# Solar_supply.net
KiCad netlist of a schematic drawn in Altium Designer
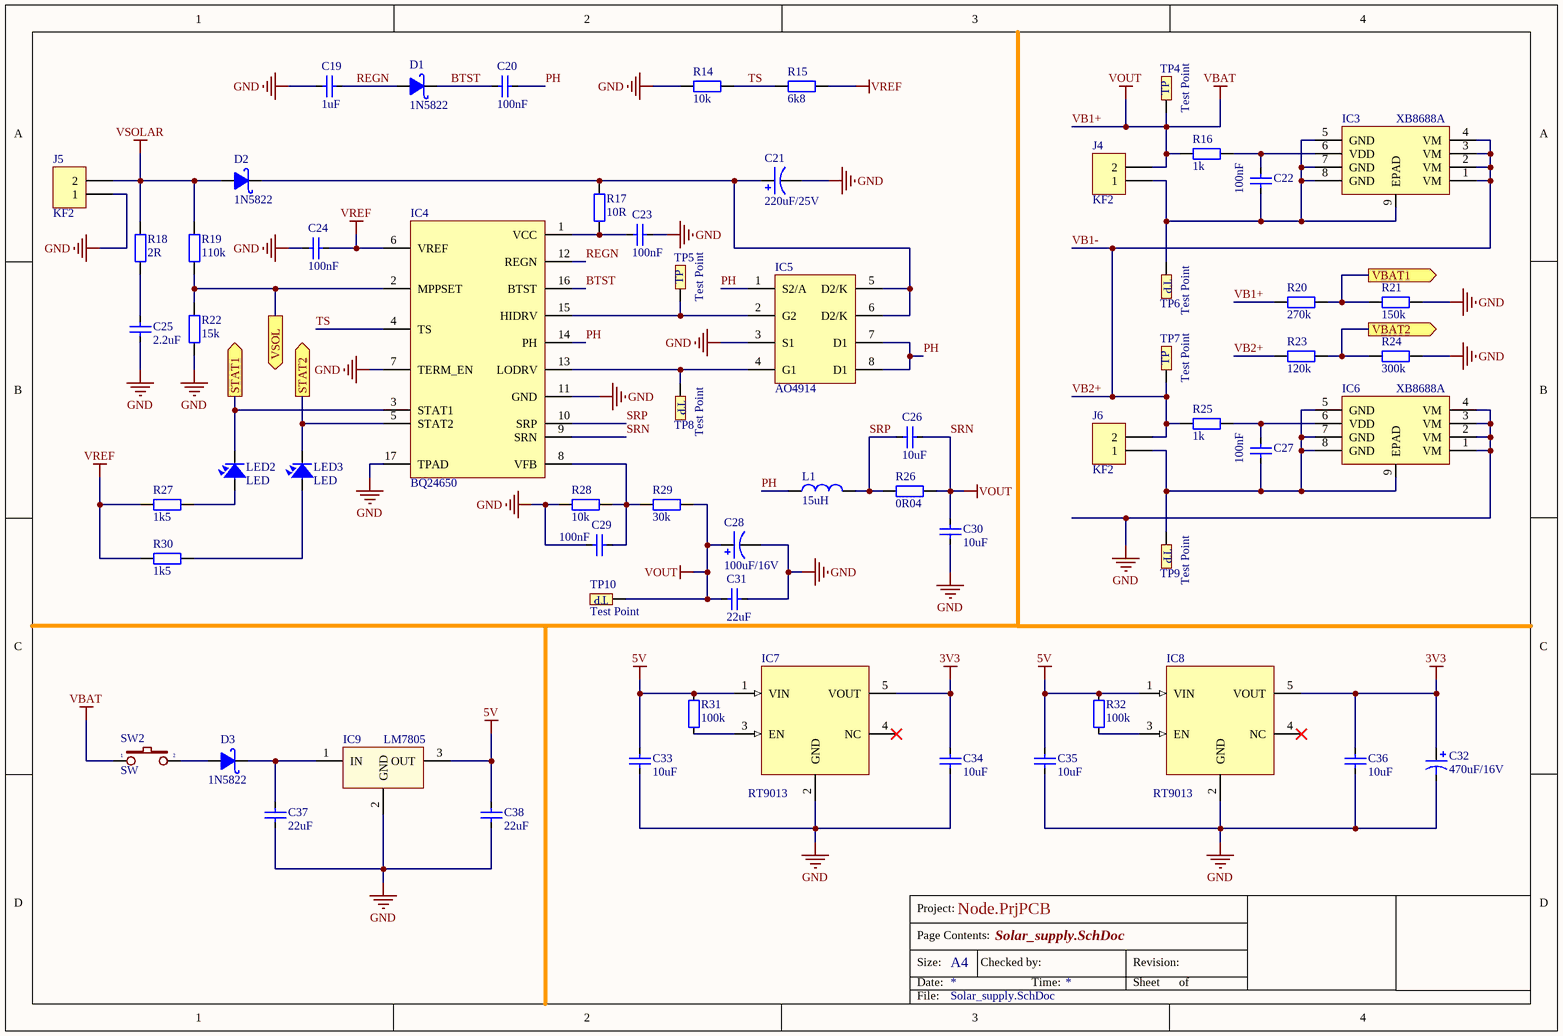
[diagram p0: Solar_supply.SchDoc]

(export (version "E")
  (design (tool "Eeschema 10.0.6"))
  (components
    (comp (ref "C19")
      (value "1uF")
      (footprint "CAP_0805")
      (description "Capacitor")
      (fields (field (name "PUBLISHER") "Altium Limited"))
      (libsource (lib "My Library") (part "CapSMD"))
    )
    (comp (ref "C20")
      (value "100nF")
      (footprint "CAP_0805")
      (description "Capacitor")
      (fields (field (name "PUBLISHER") "Altium Limited"))
      (libsource (lib "My Library") (part "CapSMD"))
    )
    (comp (ref "C21")
      (value "220uF/25V")
      (footprint "C5mm")
      (description "Polarized Capacitor (Axial)")
      (fields (field (name "PUBLISHER") "Altium Limited"))
      (libsource (lib "My Library") (part "Cap Pol"))
    )
    (comp (ref "C22")
      (value "100nF")
      (footprint "CAP_0805")
      (description "Capacitor")
      (fields (field (name "PUBLISHER") "Altium Limited"))
      (libsource (lib "My Library") (part "CapSMD"))
    )
    (comp (ref "C23")
      (value "100nF")
      (footprint "CAP_0805")
      (description "Capacitor")
      (fields (field (name "PUBLISHER") "Altium Limited"))
      (libsource (lib "My Library") (part "CapSMD"))
    )
    (comp (ref "C24")
      (value "100nF")
      (footprint "CAP_0805")
      (description "Capacitor")
      (fields (field (name "PUBLISHER") "Altium Limited"))
      (libsource (lib "My Library") (part "CapSMD"))
    )
    (comp (ref "C25")
      (value "2.2uF")
      (footprint "CAP_0805")
      (description "Capacitor")
      (fields (field (name "PUBLISHER") "Altium Limited"))
      (libsource (lib "My Library") (part "CapSMD"))
    )
    (comp (ref "C26")
      (value "10uF")
      (footprint "CAP_0805")
      (description "Capacitor")
      (fields (field (name "PUBLISHER") "Altium Limited"))
      (libsource (lib "My Library") (part "CapSMD"))
    )
    (comp (ref "C27")
      (value "100nF")
      (footprint "CAP_0805")
      (description "Capacitor")
      (fields (field (name "PUBLISHER") "Altium Limited"))
      (libsource (lib "My Library") (part "CapSMD"))
    )
    (comp (ref "C28")
      (value "100uF/16V")
      (footprint "C5mm")
      (description "Polarized Capacitor (Axial)")
      (fields (field (name "PUBLISHER") "Altium Limited"))
      (libsource (lib "My Library") (part "Cap Pol"))
    )
    (comp (ref "C29")
      (value "100nF")
      (footprint "CAP_0805")
      (description "Capacitor")
      (fields (field (name "PUBLISHER") "Altium Limited"))
      (libsource (lib "My Library") (part "CapSMD"))
    )
    (comp (ref "C30")
      (value "10uF")
      (footprint "CAP_0805")
      (description "Capacitor")
      (fields (field (name "PUBLISHER") "Altium Limited"))
      (libsource (lib "My Library") (part "CapSMD"))
    )
    (comp (ref "C31")
      (value "22uF")
      (footprint "CAP_0805")
      (description "Capacitor")
      (fields (field (name "PUBLISHER") "Altium Limited"))
      (libsource (lib "My Library") (part "CapSMD"))
    )
    (comp (ref "C32")
      (value "470uF/16V")
      (footprint "C8mm")
      (description "Polarized Capacitor (Axial)")
      (fields (field (name "PUBLISHER") "Altium Limited"))
      (libsource (lib "") (part "Cap Pol_1"))
    )
    (comp (ref "C33")
      (value "10uF")
      (footprint "CAP_0805")
      (description "Capacitor")
      (fields (field (name "PUBLISHER") "Altium Limited"))
      (libsource (lib "My Library") (part "CapSMD"))
    )
    (comp (ref "C34")
      (value "10uF")
      (footprint "CAP_0805")
      (description "Capacitor")
      (fields (field (name "PUBLISHER") "Altium Limited"))
      (libsource (lib "My Library") (part "CapSMD"))
    )
    (comp (ref "C35")
      (value "10uF")
      (footprint "CAP_0805")
      (description "Capacitor")
      (fields (field (name "PUBLISHER") "Altium Limited"))
      (libsource (lib "My Library") (part "CapSMD"))
    )
    (comp (ref "C36")
      (value "10uF")
      (footprint "CAP_0805")
      (description "Capacitor")
      (fields (field (name "PUBLISHER") "Altium Limited"))
      (libsource (lib "My Library") (part "CapSMD"))
    )
    (comp (ref "C37")
      (value "22uF")
      (footprint "CAP_0805")
      (description "Capacitor")
      (fields (field (name "PUBLISHER") "Altium Limited"))
      (libsource (lib "My Library") (part "CapSMD"))
    )
    (comp (ref "C38")
      (value "22uF")
      (footprint "CAP_0805")
      (description "Capacitor")
      (fields (field (name "PUBLISHER") "Altium Limited"))
      (libsource (lib "My Library") (part "CapSMD"))
    )
    (comp (ref "D1")
      (value "1N5822")
      (footprint "DIO-214AC(SMA)")
      (description "Schottky Rectifiers")
      (libsource (lib "My Library") (part "1N5822"))
    )
    (comp (ref "D2")
      (value "1N5822")
      (footprint "DIO-214AC(SMA)")
      (description "Schottky Rectifiers")
      (libsource (lib "My Library") (part "1N5822"))
    )
    (comp (ref "D3")
      (value "1N5822")
      (footprint "DIO-214AC(SMA)")
      (description "Schottky Rectifiers")
      (libsource (lib "My Library") (part "1N5822"))
    )
    (comp (ref "IC3")
      (value "XB8688A")
      (footprint "SOP8-PP")
      (description "One Cell Lithium-ion/Polymer Battery Protection IC")
      (libsource (lib "My Library") (part "XB8688"))
    )
    (comp (ref "IC4") (value "BQ24650") (footprint "VQFN-16") (libsource (lib "My Library") (part "BQ24650")))
    (comp (ref "IC5")
      (value "AO4914")
      (footprint "SOIC-8")
      (description "Dual N-Channel Enhancement Mode Field Effect Transistor with Schottky Diode")
      (libsource (lib "My Library") (part "AO4914"))
    )
    (comp (ref "IC6")
      (value "XB8688A")
      (footprint "SOP8-PP")
      (description "One Cell Lithium-ion/Polymer Battery Protection IC")
      (libsource (lib "My Library") (part "XB8688"))
    )
    (comp (ref "IC7")
      (value "RT9013")
      (footprint "SOT23-5")
      (description "RT9013-33GB IC REG LINEAR 3.3V 500mA SOT23-5")
      (libsource (lib "My Library") (part "RT9013"))
    )
    (comp (ref "IC8")
      (value "RT9013")
      (footprint "SOT23-5")
      (description "RT9013-33GB IC REG LINEAR 3.3V 500mA SOT23-5")
      (libsource (lib "My Library") (part "RT9013"))
    )
    (comp (ref "IC9")
      (value "LM7805")
      (footprint "TO-252")
      (description "LDO to 5V")
      (libsource (lib "My Library") (part "LM78xx"))
    )
    (comp (ref "J4")
      (value "KF2")
      (footprint "KF2-5.08")
      (fields
        (field (name "MANUFACTURER") "Würth Elektronik eiSos GmbH")
        (field (name "PARTNO") "691103110002")
        (field (name "CREATED BY") "Karrer Zheng")
      )
      (libsource (lib "My Library") (part "KF2"))
    )
    (comp (ref "J5")
      (value "KF2")
      (footprint "KF2-5.08")
      (fields
        (field (name "MANUFACTURER") "Würth Elektronik eiSos GmbH")
        (field (name "PARTNO") "691103110002")
        (field (name "CREATED BY") "Karrer Zheng")
      )
      (libsource (lib "My Library") (part "KF2"))
    )
    (comp (ref "J6")
      (value "KF2")
      (footprint "KF2-5.08")
      (fields
        (field (name "MANUFACTURER") "Würth Elektronik eiSos GmbH")
        (field (name "PARTNO") "691103110002")
        (field (name "CREATED BY") "Karrer Zheng")
      )
      (libsource (lib "My Library") (part "KF2"))
    )
    (comp (ref "L1")
      (value "15uH")
      (footprint "L-SMD-M-7.3x4.5")
      (description "Inductor")
      (libsource (lib "My Library") (part "Inductor"))
    )
    (comp (ref "LED2")
      (value "LED")
      (footprint "LED-0805-Red")
      (description "LED Single colour Green and Red")
      (libsource (lib "My Library") (part "LED"))
    )
    (comp (ref "LED3")
      (value "LED")
      (footprint "LED-0805-Orange")
      (description "LED Single colour Green and Red")
      (libsource (lib "My Library") (part "LED"))
    )
    (comp (ref "R14")
      (value "10k")
      (footprint "RES-SMD-0805")
      (description "Resistor SMD")
      (fields
        (field (name "MANUFACTURER") "Generic Components")
        (field (name "PUBLISHER") "Altium Hobart Technology Centre")
      )
      (libsource (lib "My Library") (part "Resistor - SMD"))
    )
    (comp (ref "R15")
      (value "6k8")
      (footprint "RES-SMD-0805")
      (description "Resistor SMD")
      (fields
        (field (name "MANUFACTURER") "Generic Components")
        (field (name "PUBLISHER") "Altium Hobart Technology Centre")
      )
      (libsource (lib "My Library") (part "Resistor - SMD"))
    )
    (comp (ref "R16")
      (value "1k")
      (footprint "RES-SMD-0805")
      (description "Resistor SMD")
      (fields
        (field (name "MANUFACTURER") "Generic Components")
        (field (name "PUBLISHER") "Altium Hobart Technology Centre")
      )
      (libsource (lib "My Library") (part "Resistor - SMD"))
    )
    (comp (ref "R17")
      (value "10R")
      (footprint "RES-SMD-0805")
      (description "Resistor SMD")
      (fields
        (field (name "MANUFACTURER") "Generic Components")
        (field (name "PUBLISHER") "Altium Hobart Technology Centre")
      )
      (libsource (lib "My Library") (part "Resistor - SMD"))
    )
    (comp (ref "R18")
      (value "2R")
      (footprint "RES-SMD-0805")
      (description "Resistor SMD")
      (fields
        (field (name "MANUFACTURER") "Generic Components")
        (field (name "PUBLISHER") "Altium Hobart Technology Centre")
      )
      (libsource (lib "My Library") (part "Resistor - SMD"))
    )
    (comp (ref "R19")
      (value "110k")
      (footprint "RES-SMD-0805")
      (description "Resistor SMD")
      (fields
        (field (name "MANUFACTURER") "Generic Components")
        (field (name "PUBLISHER") "Altium Hobart Technology Centre")
      )
      (libsource (lib "My Library") (part "Resistor - SMD"))
    )
    (comp (ref "R20")
      (value "270k")
      (footprint "RES-SMD-0805")
      (description "Resistor SMD")
      (fields
        (field (name "MANUFACTURER") "Generic Components")
        (field (name "PUBLISHER") "Altium Hobart Technology Centre")
      )
      (libsource (lib "My Library") (part "Resistor - SMD"))
    )
    (comp (ref "R21")
      (value "150k")
      (footprint "RES-SMD-0805")
      (description "Resistor SMD")
      (fields
        (field (name "MANUFACTURER") "Generic Components")
        (field (name "PUBLISHER") "Altium Hobart Technology Centre")
      )
      (libsource (lib "My Library") (part "Resistor - SMD"))
    )
    (comp (ref "R22")
      (value "15k")
      (footprint "RES-SMD-0805")
      (description "Resistor SMD")
      (fields
        (field (name "MANUFACTURER") "Generic Components")
        (field (name "PUBLISHER") "Altium Hobart Technology Centre")
      )
      (libsource (lib "My Library") (part "Resistor - SMD"))
    )
    (comp (ref "R23")
      (value "120k")
      (footprint "RES-SMD-0805")
      (description "Resistor SMD")
      (fields
        (field (name "MANUFACTURER") "Generic Components")
        (field (name "PUBLISHER") "Altium Hobart Technology Centre")
      )
      (libsource (lib "My Library") (part "Resistor - SMD"))
    )
    (comp (ref "R24")
      (value "300k")
      (footprint "RES-SMD-0805")
      (description "Resistor SMD")
      (fields
        (field (name "MANUFACTURER") "Generic Components")
        (field (name "PUBLISHER") "Altium Hobart Technology Centre")
      )
      (libsource (lib "My Library") (part "Resistor - SMD"))
    )
    (comp (ref "R25")
      (value "1k")
      (footprint "RES-SMD-0805")
      (description "Resistor SMD")
      (fields
        (field (name "MANUFACTURER") "Generic Components")
        (field (name "PUBLISHER") "Altium Hobart Technology Centre")
      )
      (libsource (lib "My Library") (part "Resistor - SMD"))
    )
    (comp (ref "R26")
      (value "0R04")
      (footprint "RES-SMD-2512")
      (description "Resistor SMD")
      (fields
        (field (name "MANUFACTURER") "Generic Components")
        (field (name "PUBLISHER") "Altium Hobart Technology Centre")
      )
      (libsource (lib "My Library") (part "Resistor - SMD"))
    )
    (comp (ref "R27")
      (value "1k5")
      (footprint "RES-SMD-0805")
      (description "Resistor SMD")
      (fields
        (field (name "MANUFACTURER") "Generic Components")
        (field (name "PUBLISHER") "Altium Hobart Technology Centre")
      )
      (libsource (lib "My Library") (part "Resistor - SMD"))
    )
    (comp (ref "R28")
      (value "10k")
      (footprint "RES-SMD-0805")
      (description "Resistor SMD")
      (fields
        (field (name "MANUFACTURER") "Generic Components")
        (field (name "PUBLISHER") "Altium Hobart Technology Centre")
      )
      (libsource (lib "My Library") (part "Resistor - SMD"))
    )
    (comp (ref "R29")
      (value "30k")
      (footprint "RES-SMD-0805")
      (description "Resistor SMD")
      (fields
        (field (name "MANUFACTURER") "Generic Components")
        (field (name "PUBLISHER") "Altium Hobart Technology Centre")
      )
      (libsource (lib "My Library") (part "Resistor - SMD"))
    )
    (comp (ref "R30")
      (value "1k5")
      (footprint "RES-SMD-0805")
      (description "Resistor SMD")
      (fields
        (field (name "MANUFACTURER") "Generic Components")
        (field (name "PUBLISHER") "Altium Hobart Technology Centre")
      )
      (libsource (lib "My Library") (part "Resistor - SMD"))
    )
    (comp (ref "R31")
      (value "100k")
      (footprint "RES-SMD-0805")
      (description "Resistor")
      (fields
        (field (name "MANUFACTURER") "Generic Components")
        (field (name "PUBLISHER") "Altium Hobart Technology Centre")
      )
      (libsource (lib "") (part "Resistor - SMD_1"))
    )
    (comp (ref "R32")
      (value "100k")
      (footprint "RES-SMD-0805")
      (description "Resistor")
      (fields
        (field (name "MANUFACTURER") "Generic Components")
        (field (name "PUBLISHER") "Altium Hobart Technology Centre")
      )
      (libsource (lib "") (part "Resistor - SMD_1"))
    )
    (comp (ref "SW2")
      (value "SW")
      (footprint "SW2")
      (description "Switch button 2 pin")
      (libsource (lib "My Library") (part "SW2"))
    )
    (comp (ref "TP4")
      (value "Test Point")
      (footprint "TP_SMD")
      (description "CONNECT 1")
      (libsource (lib "My Library") (part "TP"))
    )
    (comp (ref "TP5")
      (value "Test Point")
      (footprint "TP_SMD")
      (description "CONNECT 1")
      (libsource (lib "My Library") (part "TP"))
    )
    (comp (ref "TP6")
      (value "Test Point")
      (footprint "TP_SMD")
      (description "CONNECT 1")
      (libsource (lib "") (part "TP_1"))
    )
    (comp (ref "TP7")
      (value "Test Point")
      (footprint "TP_SMD")
      (description "CONNECT 1")
      (libsource (lib "My Library") (part "TP"))
    )
    (comp (ref "TP8")
      (value "Test Point")
      (footprint "TP_SMD")
      (description "CONNECT 1")
      (libsource (lib "") (part "TP_1"))
    )
    (comp (ref "TP9")
      (value "Test Point")
      (footprint "TP_SMD")
      (description "CONNECT 1")
      (libsource (lib "") (part "TP_1"))
    )
    (comp (ref "TP10")
      (value "Test Point")
      (footprint "TP_SMD")
      (description "CONNECT 1")
      (libsource (lib "") (part "TP_2"))
    )
  )
  (nets
    (net (code "1") (name "/BTST") (class "Default")
      (node (ref "C20") (pin "1") (pinfunction "1_1") (pintype "passive"))
      (node (ref "D1") (pin "2") (pinfunction "K_2") (pintype "passive"))
      (node (ref "IC4") (pin "16") (pinfunction "BTST_16") (pintype "passive"))
    )
    (net (code "2") (name "/PH") (class "Default")
      (node (ref "C20") (pin "2") (pinfunction "2_2") (pintype "passive"))
      (node (ref "IC4") (pin "14") (pinfunction "PH_14") (pintype "passive"))
      (node (ref "IC5") (pin "1") (pinfunction "S2/A_1") (pintype "passive"))
      (node (ref "IC5") (pin "7") (pinfunction "D1_7") (pintype "passive"))
      (node (ref "IC5") (pin "8") (pinfunction "D1_8") (pintype "passive"))
      (node (ref "L1") (pin "1") (pinfunction "1_1") (pintype "passive"))
    )
    (net (code "3") (name "/REGN") (class "Default")
      (node (ref "C19") (pin "1") (pinfunction "1_1") (pintype "passive"))
      (node (ref "D1") (pin "1") (pinfunction "A_1") (pintype "passive"))
      (node (ref "IC4") (pin "12") (pinfunction "REGN_12") (pintype "passive"))
    )
    (net (code "4") (name "/SRP") (class "Default")
      (node (ref "C26") (pin "2") (pinfunction "2_2") (pintype "passive"))
      (node (ref "IC4") (pin "10") (pinfunction "SRP_10") (pintype "passive"))
      (node (ref "L1") (pin "2") (pinfunction "2_2") (pintype "passive"))
      (node (ref "R26") (pin "1") (pinfunction "1_1") (pintype "passive"))
    )
    (net (code "5") (name "/STAT1") (class "Default")
      (node (ref "IC4") (pin "3") (pinfunction "STAT1_3") (pintype "passive"))
      (node (ref "LED2") (pin "2") (pinfunction "2_2") (pintype "passive"))
    )
    (net (code "6") (name "/STAT2") (class "Default")
      (node (ref "IC4") (pin "5") (pinfunction "STAT2_5") (pintype "passive"))
      (node (ref "LED3") (pin "2") (pinfunction "2_2") (pintype "passive"))
    )
    (net (code "7") (name "/TS") (class "Default")
      (node (ref "IC4") (pin "4") (pinfunction "TS_4") (pintype "passive"))
      (node (ref "R14") (pin "2") (pinfunction "2_2") (pintype "passive"))
      (node (ref "R15") (pin "1") (pinfunction "1_1") (pintype "passive"))
    )
    (net (code "8") (name "/VB1-") (class "Default")
      (node (ref "IC3") (pin "1") (pinfunction "VM_1") (pintype "passive"))
      (node (ref "IC3") (pin "2") (pinfunction "VM_2") (pintype "passive"))
      (node (ref "IC3") (pin "3") (pinfunction "VM_3") (pintype "passive"))
      (node (ref "IC3") (pin "4") (pinfunction "VM_4") (pintype "passive"))
      (node (ref "J6") (pin "2") (pinfunction "2_2") (pintype "passive"))
      (node (ref "R23") (pin "2") (pinfunction "2_2") (pintype "passive"))
      (node (ref "R25") (pin "2") (pinfunction "2_2") (pintype "passive"))
      (node (ref "TP7") (pin "1") (pinfunction "0_1") (pintype "passive"))
    )
    (net (code "9") (name "/VBAT1") (class "Default")
      (node (ref "R20") (pin "1") (pinfunction "1_1") (pintype "passive"))
      (node (ref "R21") (pin "2") (pinfunction "2_2") (pintype "passive"))
    )
    (net (code "10") (name "/VBAT2") (class "Default")
      (node (ref "R23") (pin "1") (pinfunction "1_1") (pintype "passive"))
      (node (ref "R24") (pin "2") (pinfunction "2_2") (pintype "passive"))
    )
    (net (code "11") (name "/VSOL") (class "Default")
      (node (ref "IC4") (pin "2") (pinfunction "MPPSET_2") (pintype "passive"))
      (node (ref "R19") (pin "1") (pinfunction "1_1") (pintype "passive"))
      (node (ref "R22") (pin "1") (pinfunction "1_1") (pintype "passive"))
    )
    (net (code "12") (name "3V3") (class "Default")
      (node (ref "C32") (pin "1") (pinfunction "1_1") (pintype "passive"))
      (node (ref "C34") (pin "2") (pinfunction "2_2") (pintype "passive"))
      (node (ref "C36") (pin "2") (pinfunction "2_2") (pintype "passive"))
      (node (ref "IC7") (pin "5") (pinfunction "VOUT_5") (pintype "power_in"))
      (node (ref "IC8") (pin "5") (pinfunction "VOUT_5") (pintype "power_in"))
    )
    (net (code "13") (name "5V") (class "Default")
      (node (ref "C33") (pin "2") (pinfunction "2_2") (pintype "passive"))
      (node (ref "C35") (pin "2") (pinfunction "2_2") (pintype "passive"))
      (node (ref "C38") (pin "2") (pinfunction "2_2") (pintype "passive"))
      (node (ref "IC7") (pin "1") (pinfunction "VIN_1") (pintype "input"))
      (node (ref "IC8") (pin "1") (pinfunction "VIN_1") (pintype "input"))
      (node (ref "IC9") (pin "3") (pinfunction "OUT_3") (pintype "passive"))
      (node (ref "R31") (pin "1") (pinfunction "1_1") (pintype "passive"))
      (node (ref "R32") (pin "1") (pinfunction "1_1") (pintype "passive"))
    )
    (net (code "14") (name "GND") (class "Default")
      (node (ref "C19") (pin "2") (pinfunction "2_2") (pintype "passive"))
      (node (ref "C21") (pin "2") (pinfunction "2_2") (pintype "passive"))
      (node (ref "C23") (pin "2") (pinfunction "2_2") (pintype "passive"))
      (node (ref "C24") (pin "2") (pinfunction "2_2") (pintype "passive"))
      (node (ref "C25") (pin "1") (pinfunction "1_1") (pintype "passive"))
      (node (ref "C28") (pin "2") (pinfunction "2_2") (pintype "passive"))
      (node (ref "C29") (pin "1") (pinfunction "1_1") (pintype "passive"))
      (node (ref "C30") (pin "1") (pinfunction "1_1") (pintype "passive"))
      (node (ref "C31") (pin "1") (pinfunction "1_1") (pintype "passive"))
      (node (ref "C32") (pin "2") (pinfunction "2_2") (pintype "passive"))
      (node (ref "C33") (pin "1") (pinfunction "1_1") (pintype "passive"))
      (node (ref "C34") (pin "1") (pinfunction "1_1") (pintype "passive"))
      (node (ref "C35") (pin "1") (pinfunction "1_1") (pintype "passive"))
      (node (ref "C36") (pin "1") (pinfunction "1_1") (pintype "passive"))
      (node (ref "C37") (pin "1") (pinfunction "1_1") (pintype "passive"))
      (node (ref "C38") (pin "1") (pinfunction "1_1") (pintype "passive"))
      (node (ref "IC4") (pin "11") (pinfunction "GND_11") (pintype "passive"))
      (node (ref "IC4") (pin "17") (pinfunction "TPAD_17") (pintype "passive"))
      (node (ref "IC4") (pin "7") (pinfunction "TERM_EN_7") (pintype "passive"))
      (node (ref "IC5") (pin "3") (pinfunction "S1_3") (pintype "passive"))
      (node (ref "IC6") (pin "1") (pinfunction "VM_1") (pintype "passive"))
      (node (ref "IC6") (pin "2") (pinfunction "VM_2") (pintype "passive"))
      (node (ref "IC6") (pin "3") (pinfunction "VM_3") (pintype "passive"))
      (node (ref "IC6") (pin "4") (pinfunction "VM_4") (pintype "passive"))
      (node (ref "IC7") (pin "2") (pinfunction "GND_2") (pintype "passive"))
      (node (ref "IC8") (pin "2") (pinfunction "GND_2") (pintype "passive"))
      (node (ref "IC9") (pin "2") (pinfunction "GND_2") (pintype "passive"))
      (node (ref "J5") (pin "1") (pinfunction "1_1") (pintype "passive"))
      (node (ref "R14") (pin "1") (pinfunction "1_1") (pintype "passive"))
      (node (ref "R21") (pin "1") (pinfunction "1_1") (pintype "passive"))
      (node (ref "R22") (pin "2") (pinfunction "2_2") (pintype "passive"))
      (node (ref "R24") (pin "1") (pinfunction "1_1") (pintype "passive"))
      (node (ref "R28") (pin "1") (pinfunction "1_1") (pintype "passive"))
    )
    (net (code "15") (name "Net-(C25-Pad2)") (class "Default")
      (node (ref "C25") (pin "2") (pinfunction "2_2") (pintype "passive"))
      (node (ref "R18") (pin "2") (pinfunction "2_2") (pintype "passive"))
    )
    (net (code "16") (name "Net-(D2-K)") (class "Default")
      (node (ref "C21") (pin "1") (pinfunction "1_1") (pintype "passive"))
      (node (ref "D2") (pin "2") (pinfunction "K_2") (pintype "passive"))
      (node (ref "IC5") (pin "5") (pinfunction "D2/K_5") (pintype "passive"))
      (node (ref "IC5") (pin "6") (pinfunction "D2/K_6") (pintype "passive"))
      (node (ref "R17") (pin "1") (pinfunction "1_1") (pintype "passive"))
    )
    (net (code "17") (name "Net-(D3-A)") (class "Default")
      (node (ref "D3") (pin "1") (pinfunction "A_1") (pintype "passive"))
      (node (ref "SW2") (pin "2") (pinfunction "2_2") (pintype "passive"))
    )
    (net (code "18") (name "Net-(D3-K)") (class "Default")
      (node (ref "C37") (pin "2") (pinfunction "2_2") (pintype "passive"))
      (node (ref "D3") (pin "2") (pinfunction "K_2") (pintype "passive"))
      (node (ref "IC9") (pin "1") (pinfunction "IN_1") (pintype "passive"))
    )
    (net (code "19") (name "Net-(IC3-EPAD)") (class "Default")
      (node (ref "C22") (pin "1") (pinfunction "1_1") (pintype "passive"))
      (node (ref "IC3") (pin "5") (pinfunction "GND_5") (pintype "passive"))
      (node (ref "IC3") (pin "7") (pinfunction "GND_7") (pintype "passive"))
      (node (ref "IC3") (pin "8") (pinfunction "GND_8") (pintype "passive"))
      (node (ref "IC3") (pin "9") (pinfunction "EPAD_9") (pintype "passive"))
      (node (ref "J4") (pin "1") (pinfunction "1_1") (pintype "passive"))
      (node (ref "TP6") (pin "1") (pinfunction "0_1") (pintype "passive"))
    )
    (net (code "20") (name "Net-(IC3-VDD)") (class "Default")
      (node (ref "C22") (pin "2") (pinfunction "2_2") (pintype "passive"))
      (node (ref "IC3") (pin "6") (pinfunction "VDD_6") (pintype "passive"))
      (node (ref "R16") (pin "1") (pinfunction "1_1") (pintype "passive"))
    )
    (net (code "21") (name "Net-(IC4-HIDRV)") (class "Default")
      (node (ref "IC4") (pin "15") (pinfunction "HIDRV_15") (pintype "passive"))
      (node (ref "IC5") (pin "2") (pinfunction "G2_2") (pintype "passive"))
      (node (ref "TP5") (pin "1") (pinfunction "0_1") (pintype "passive"))
    )
    (net (code "22") (name "Net-(IC4-LODRV)") (class "Default")
      (node (ref "IC4") (pin "13") (pinfunction "LODRV_13") (pintype "passive"))
      (node (ref "IC5") (pin "4") (pinfunction "G1_4") (pintype "passive"))
      (node (ref "TP8") (pin "1") (pinfunction "0_1") (pintype "passive"))
    )
    (net (code "23") (name "Net-(IC4-VCC)") (class "Default")
      (node (ref "C23") (pin "1") (pinfunction "1_1") (pintype "passive"))
      (node (ref "IC4") (pin "1") (pinfunction "VCC_1") (pintype "passive"))
      (node (ref "R17") (pin "2") (pinfunction "2_2") (pintype "passive"))
    )
    (net (code "24") (name "Net-(IC4-VFB)") (class "Default")
      (node (ref "C29") (pin "2") (pinfunction "2_2") (pintype "passive"))
      (node (ref "IC4") (pin "8") (pinfunction "VFB_8") (pintype "passive"))
      (node (ref "R28") (pin "2") (pinfunction "2_2") (pintype "passive"))
      (node (ref "R29") (pin "2") (pinfunction "2_2") (pintype "passive"))
    )
    (net (code "25") (name "Net-(IC6-EPAD)") (class "Default")
      (node (ref "C27") (pin "1") (pinfunction "1_1") (pintype "passive"))
      (node (ref "IC6") (pin "5") (pinfunction "GND_5") (pintype "passive"))
      (node (ref "IC6") (pin "7") (pinfunction "GND_7") (pintype "passive"))
      (node (ref "IC6") (pin "8") (pinfunction "GND_8") (pintype "passive"))
      (node (ref "IC6") (pin "9") (pinfunction "EPAD_9") (pintype "passive"))
      (node (ref "J6") (pin "1") (pinfunction "1_1") (pintype "passive"))
      (node (ref "TP9") (pin "1") (pinfunction "0_1") (pintype "passive"))
    )
    (net (code "26") (name "Net-(IC6-VDD)") (class "Default")
      (node (ref "C27") (pin "2") (pinfunction "2_2") (pintype "passive"))
      (node (ref "IC6") (pin "6") (pinfunction "VDD_6") (pintype "passive"))
      (node (ref "R25") (pin "1") (pinfunction "1_1") (pintype "passive"))
    )
    (net (code "27") (name "Net-(IC7-EN)") (class "Default")
      (node (ref "IC7") (pin "3") (pinfunction "EN_3") (pintype "input"))
      (node (ref "R31") (pin "2") (pinfunction "2_2") (pintype "passive"))
    )
    (net (code "28") (name "Net-(IC8-EN)") (class "Default")
      (node (ref "IC8") (pin "3") (pinfunction "EN_3") (pintype "input"))
      (node (ref "R32") (pin "2") (pinfunction "2_2") (pintype "passive"))
    )
    (net (code "29") (name "Net-(LED2-Pad1)") (class "Default")
      (node (ref "LED2") (pin "1") (pinfunction "1_1") (pintype "passive"))
      (node (ref "R27") (pin "2") (pinfunction "2_2") (pintype "passive"))
    )
    (net (code "30") (name "Net-(LED3-Pad1)") (class "Default")
      (node (ref "LED3") (pin "1") (pinfunction "1_1") (pintype "passive"))
      (node (ref "R30") (pin "2") (pinfunction "2_2") (pintype "passive"))
    )
    (net (code "31") (name "VBAT") (class "Default")
      (node (ref "C26") (pin "1") (pinfunction "1_1") (pintype "passive"))
      (node (ref "C28") (pin "1") (pinfunction "1_1") (pintype "passive"))
      (node (ref "C30") (pin "2") (pinfunction "2_2") (pintype "passive"))
      (node (ref "C31") (pin "2") (pinfunction "2_2") (pintype "passive"))
      (node (ref "IC4") (pin "9") (pinfunction "SRN_9") (pintype "passive"))
      (node (ref "J4") (pin "2") (pinfunction "2_2") (pintype "passive"))
      (node (ref "R16") (pin "2") (pinfunction "2_2") (pintype "passive"))
      (node (ref "R20") (pin "2") (pinfunction "2_2") (pintype "passive"))
      (node (ref "R26") (pin "2") (pinfunction "2_2") (pintype "passive"))
      (node (ref "R29") (pin "1") (pinfunction "1_1") (pintype "passive"))
      (node (ref "SW2") (pin "1") (pinfunction "1_1") (pintype "passive"))
      (node (ref "TP10") (pin "1") (pinfunction "0_1") (pintype "passive"))
      (node (ref "TP4") (pin "1") (pinfunction "0_1") (pintype "passive"))
    )
    (net (code "32") (name "VREF") (class "Default")
      (node (ref "C24") (pin "1") (pinfunction "1_1") (pintype "passive"))
      (node (ref "IC4") (pin "6") (pinfunction "VREF_6") (pintype "passive"))
      (node (ref "R15") (pin "2") (pinfunction "2_2") (pintype "passive"))
      (node (ref "R27") (pin "1") (pinfunction "1_1") (pintype "passive"))
      (node (ref "R30") (pin "1") (pinfunction "1_1") (pintype "passive"))
    )
    (net (code "33") (name "VSOLAR") (class "Default")
      (node (ref "D2") (pin "1") (pinfunction "A_1") (pintype "passive"))
      (node (ref "J5") (pin "2") (pinfunction "2_2") (pintype "passive"))
      (node (ref "R18") (pin "1") (pinfunction "1_1") (pintype "passive"))
      (node (ref "R19") (pin "2") (pinfunction "2_2") (pintype "passive"))
    )
    (net (code "34") (name "unconnected-(IC7-NC-Pad4)") (class "Default")
      (node (ref "IC7") (pin "4") (pinfunction "NC_4") (pintype "passive+no_connect"))
    )
    (net (code "35") (name "unconnected-(IC8-NC-Pad4)") (class "Default")
      (node (ref "IC8") (pin "4") (pinfunction "NC_4") (pintype "passive+no_connect"))
    )
  )
)
